# ProProject__-mpu6050__2024-04-23.net
KiCad netlist of a schematic drawn in EasyEDA Pro
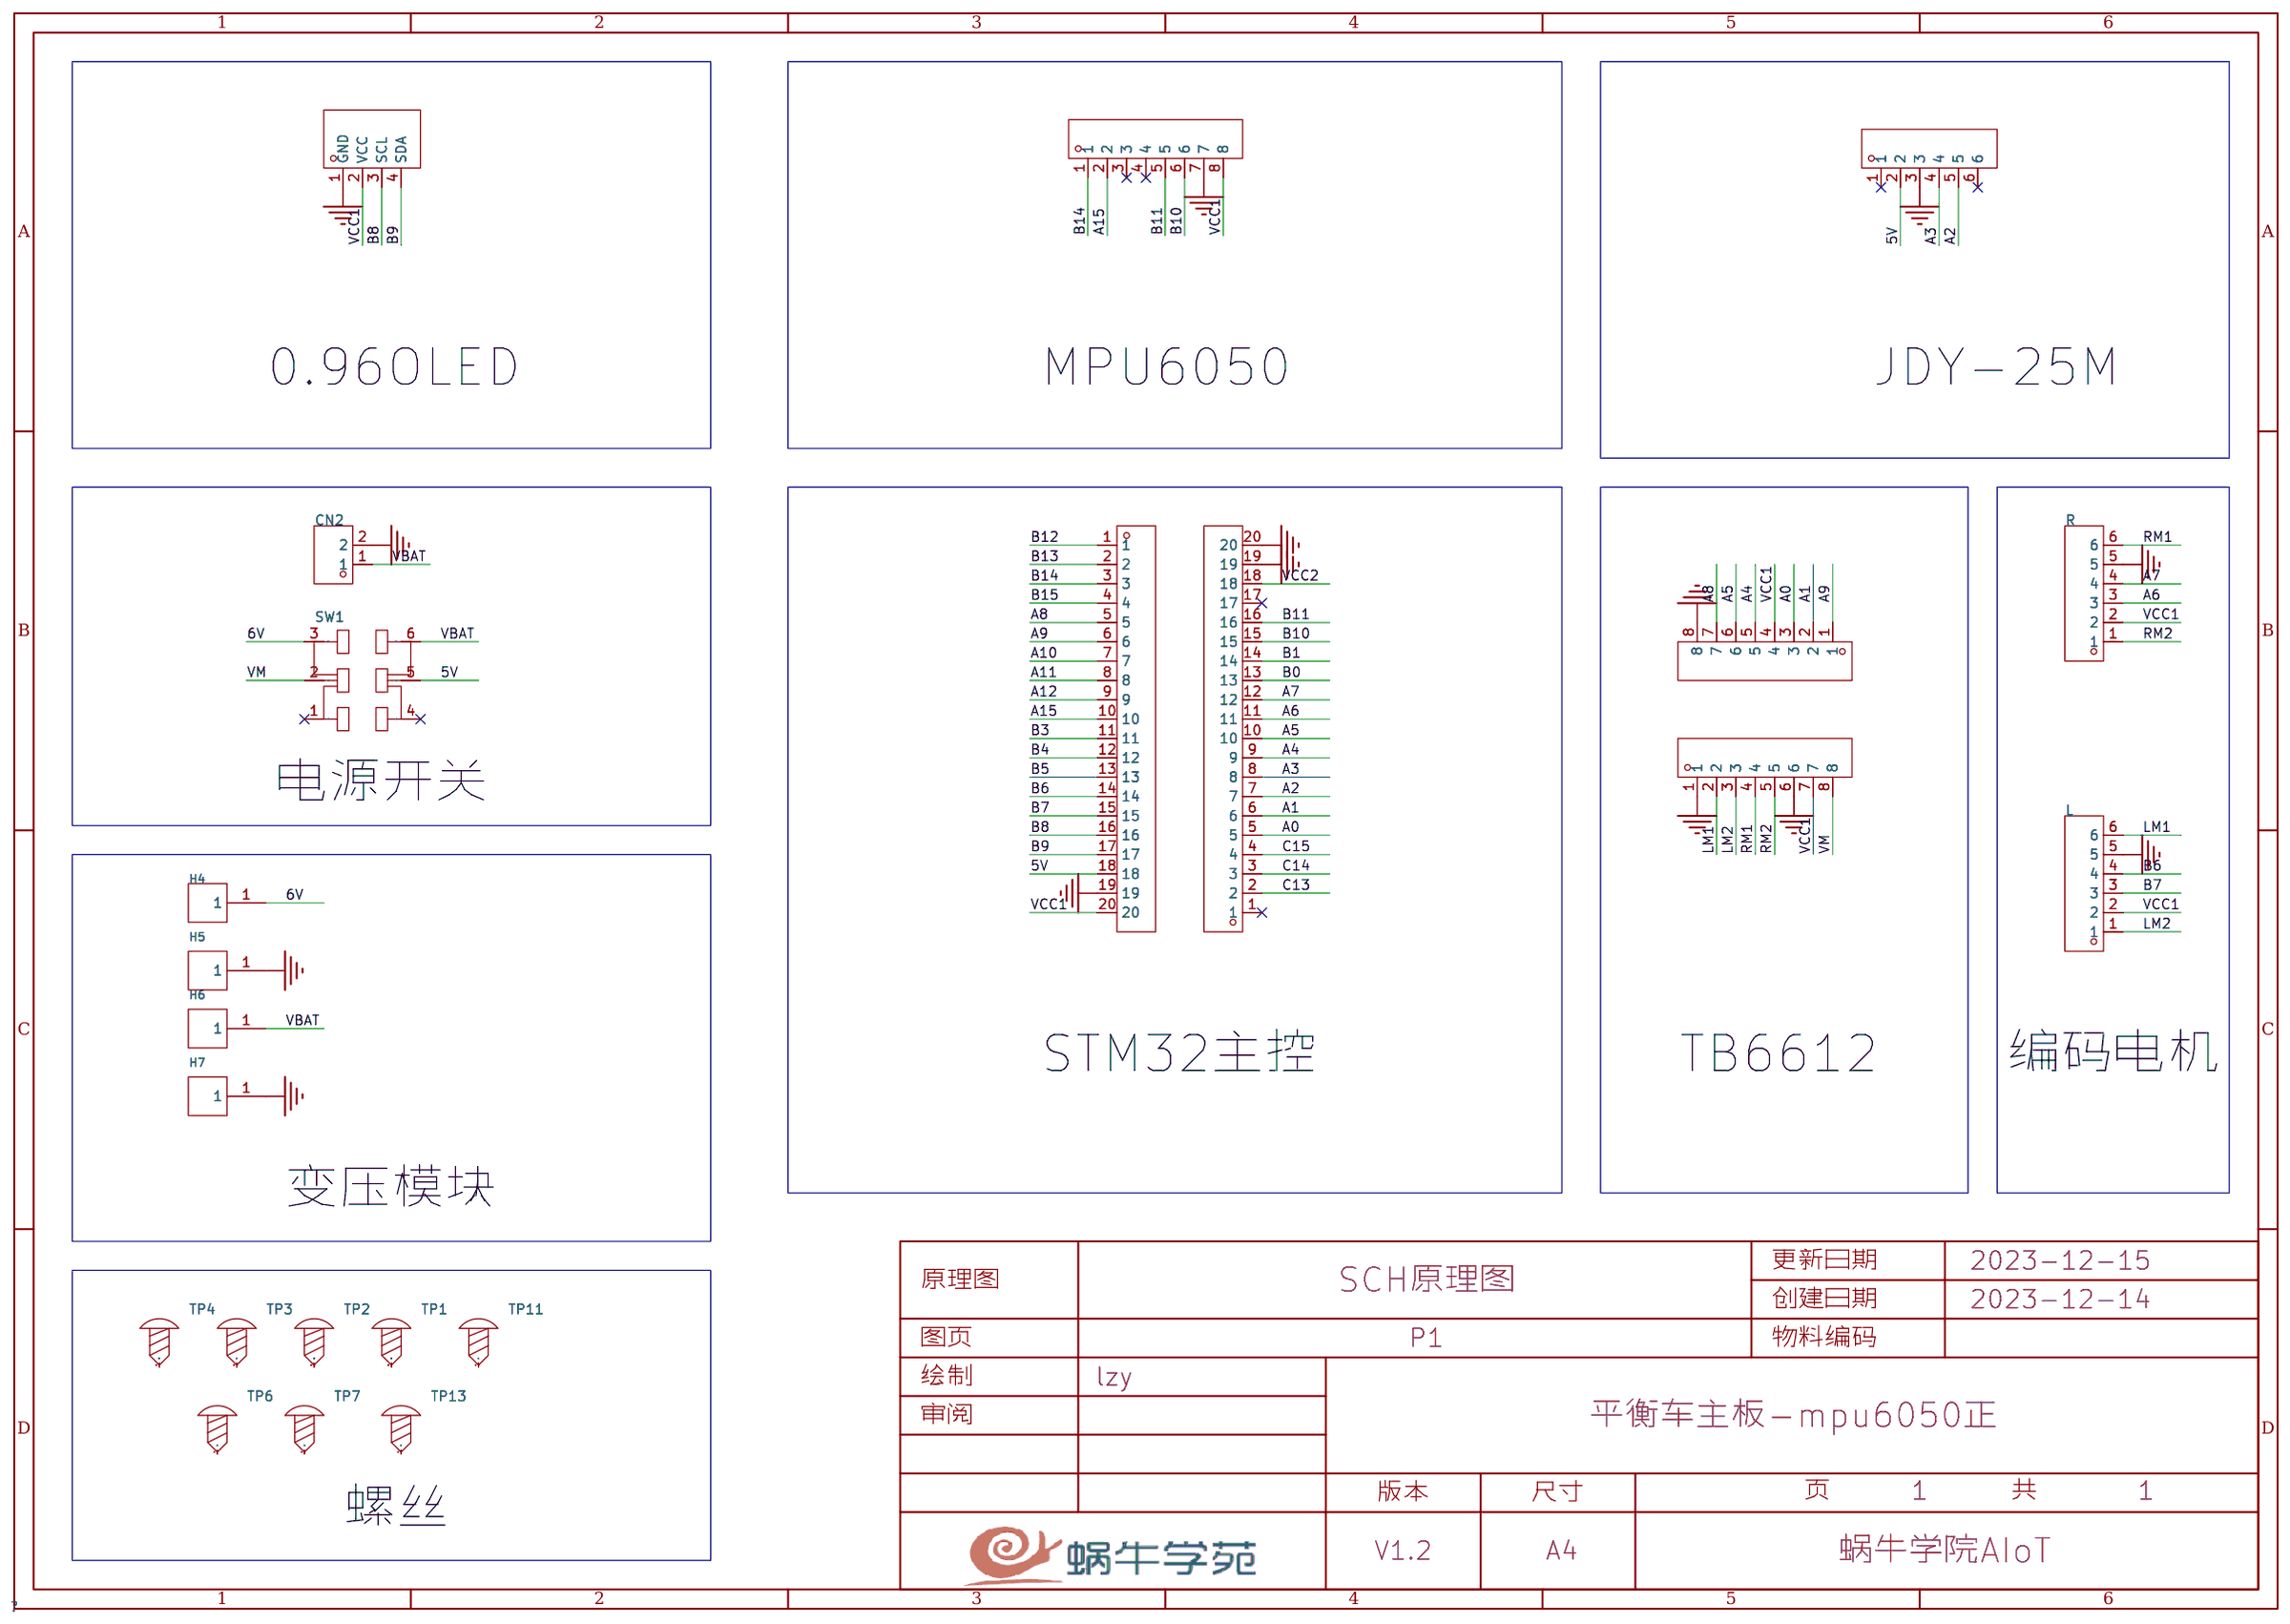
[diagram p0: schematic sheet]

(export (version "E")
  (design (tool "Eeschema 10.0.6"))
  (components
    (comp (ref "CN2")
      (value "XH-2AW")
      (footprint "easyedapro:CONN-TH_XH-2AW_C2908611")
      (description "插针结构:1x2P;间距:2.54mm;公母:公;安装方式:弯插;行距:-;排数:1;每排PIN数:2;参考系列:XH;额定电流:3A;工作温度范围:-25°C~+85°C;")
      (fields (field (name "Manufacturer") "HCTL(华灿天禄)"))
      (libsource (lib "easyedapro") (part "XH-2AW_C2908611"))
    )
    (comp (ref "H1")
      (value "PM254V-11-06-H85")
      (footprint "easyedapro:HDR-TH_6P-P2.54-V-F")
      (fields (field (name "Manufacturer") "XFCN(兴飞)"))
      (libsource (lib "easyedapro") (part "PM254V-11-06-H85"))
    )
    (comp (ref "H4")
      (value "PZ254V-11-01P")
      (footprint "easyedapro:HDR-TH_1P-P2.54-V-M")
      (fields (field (name "Manufacturer") "XFCN(兴飞)"))
      (libsource (lib "easyedapro") (part "PZ254V-11-01P"))
    )
    (comp (ref "H5")
      (value "PZ254V-11-01P")
      (footprint "easyedapro:HDR-TH_1P-P2.54-V-M")
      (fields (field (name "Manufacturer") "XFCN(兴飞)"))
      (libsource (lib "easyedapro") (part "PZ254V-11-01P"))
    )
    (comp (ref "H6")
      (value "PZ254V-11-01P")
      (footprint "easyedapro:HDR-TH_1P-P2.54-V-M")
      (fields (field (name "Manufacturer") "XFCN(兴飞)"))
      (libsource (lib "easyedapro") (part "PZ254V-11-01P"))
    )
    (comp (ref "H7")
      (value "PZ254V-11-01P")
      (footprint "easyedapro:HDR-TH_1P-P2.54-V-M")
      (fields (field (name "Manufacturer") "XFCN(兴飞)"))
      (libsource (lib "easyedapro") (part "PZ254V-11-01P"))
    )
    (comp (ref "L")
      (value "PM254V-11-06-H85")
      (footprint "easyedapro:HDR-TH_6P-P2.54-V-F")
      (fields (field (name "Manufacturer") "XFCN(兴飞)"))
      (libsource (lib "easyedapro") (part "PM254V-11-06-H85"))
    )
    (comp (ref "OLED")
      (value "HS96L03W2C03")
      (footprint "easyedapro:OLED-TH_L27.8-W27.2-P2.54_C9900033791")
      (fields (field (name "Manufacturer") "HS(汉昇)"))
      (libsource (lib "easyedapro") (part "HS96L03W2C03"))
    )
    (comp (ref "R")
      (value "PM254V-11-06-H85")
      (footprint "easyedapro:HDR-TH_6P-P2.54-V-F")
      (fields (field (name "Manufacturer") "XFCN(兴飞)"))
      (libsource (lib "easyedapro") (part "PM254V-11-06-H85"))
    )
    (comp (ref "SW1")
      (value "MSS22D18G2")
      (footprint "easyedapro:SW-TH_MSS22D18GX")
      (description "电路结构:双刀双掷;安装方式:立插;开关颜色:-;额定电流(DC):100mA;额定电压(DC):12V;额定电流(AC):-;额定电压(AC):-;机械寿命:1万次;")
      (fields (field (name "Manufacturer") "SHOU HAN(首韩)"))
      (libsource (lib "easyedapro") (part "MSS22D18G2"))
    )
    (comp (ref "TP1") (value "~") (footprint "easyedapro:M3螺丝") (libsource (lib "easyedapro") (part "螺丝孔")))
    (comp (ref "TP2") (value "~") (footprint "easyedapro:M3螺丝") (libsource (lib "easyedapro") (part "螺丝孔")))
    (comp (ref "TP3") (value "~") (footprint "easyedapro:M3螺丝") (libsource (lib "easyedapro") (part "螺丝孔")))
    (comp (ref "TP4") (value "~") (footprint "easyedapro:M3螺丝") (libsource (lib "easyedapro") (part "螺丝孔")))
    (comp (ref "TP6") (value "~") (footprint "easyedapro:M3螺丝") (libsource (lib "easyedapro") (part "螺丝孔")))
    (comp (ref "TP7") (value "~") (footprint "easyedapro:M3螺丝") (libsource (lib "easyedapro") (part "螺丝孔")))
    (comp (ref "TP11") (value "~") (footprint "easyedapro:M3螺丝") (libsource (lib "easyedapro") (part "螺丝孔")))
    (comp (ref "TP13") (value "~") (footprint "easyedapro:M3螺丝") (libsource (lib "easyedapro") (part "螺丝孔")))
    (comp (ref "U1")
      (value "PM254-1-20-Z-8.5")
      (footprint "easyedapro:HDR-TH_20P-P2.54-V-F-2")
      (fields (field (name "Manufacturer") "HCTL(华灿天禄)"))
      (libsource (lib "easyedapro") (part "PM254-1-20-Z-8.5"))
    )
    (comp (ref "U2")
      (value "PM254-1-20-Z-8.5")
      (footprint "easyedapro:HDR-TH_20P-P2.54-V-F-2")
      (fields (field (name "Manufacturer") "HCTL(华灿天禄)"))
      (libsource (lib "easyedapro") (part "PM254-1-20-Z-8.5"))
    )
    (comp (ref "U4")
      (value "PM254-1-08-Z-8.5")
      (footprint "easyedapro:HDR-TH_8P-P2.54-V-F")
      (fields (field (name "Manufacturer") "HCTL(华灿天禄)"))
      (libsource (lib "easyedapro") (part "PM254-1-08-Z-8.5"))
    )
    (comp (ref "U5")
      (value "PM254-1-08-Z-8.5")
      (footprint "easyedapro:HDR-TH_8P-P2.54-V-F")
      (fields (field (name "Manufacturer") "HCTL(华灿天禄)"))
      (libsource (lib "easyedapro") (part "PM254-1-08-Z-8.5"))
    )
    (comp (ref "U6")
      (value "PM254-1-08-Z-8.5")
      (footprint "easyedapro:HDR-TH_8P-P2.54-V-F")
      (fields (field (name "Manufacturer") "HCTL(华灿天禄)"))
      (libsource (lib "easyedapro") (part "PM254-1-08-Z-8.5"))
    )
  )
  (nets
    (net (code "1") (name "/5V") (class "Default")
      (node (ref "H1") (pin "2") (pinfunction "2_2") (pintype "unspecified"))
      (node (ref "SW1") (pin "5") (pinfunction "5_5") (pintype "unspecified"))
      (node (ref "U1") (pin "18") (pinfunction "18_18") (pintype "unspecified"))
    )
    (net (code "2") (name "/6V") (class "Default")
      (node (ref "H4") (pin "1") (pinfunction "1_1") (pintype "input"))
      (node (ref "SW1") (pin "3") (pinfunction "3_3") (pintype "unspecified"))
    )
    (net (code "3") (name "/A0") (class "Default")
      (node (ref "U2") (pin "5") (pinfunction "5_5") (pintype "unspecified"))
      (node (ref "U5") (pin "3") (pinfunction "3_3") (pintype "unspecified"))
    )
    (net (code "4") (name "/A1") (class "Default")
      (node (ref "U2") (pin "6") (pinfunction "6_6") (pintype "unspecified"))
      (node (ref "U5") (pin "2") (pinfunction "2_2") (pintype "unspecified"))
    )
    (net (code "5") (name "/A2") (class "Default")
      (node (ref "H1") (pin "5") (pinfunction "5_5") (pintype "unspecified"))
      (node (ref "U2") (pin "7") (pinfunction "7_7") (pintype "unspecified"))
    )
    (net (code "6") (name "/A3") (class "Default")
      (node (ref "H1") (pin "4") (pinfunction "4_4") (pintype "unspecified"))
      (node (ref "U2") (pin "8") (pinfunction "8_8") (pintype "unspecified"))
    )
    (net (code "7") (name "/A4") (class "Default")
      (node (ref "U2") (pin "9") (pinfunction "9_9") (pintype "unspecified"))
      (node (ref "U5") (pin "5") (pinfunction "5_5") (pintype "unspecified"))
    )
    (net (code "8") (name "/A5") (class "Default")
      (node (ref "U2") (pin "10") (pinfunction "10_10") (pintype "unspecified"))
      (node (ref "U5") (pin "6") (pinfunction "6_6") (pintype "unspecified"))
    )
    (net (code "9") (name "/A6") (class "Default")
      (node (ref "R") (pin "3") (pinfunction "3_3") (pintype "unspecified"))
      (node (ref "U2") (pin "11") (pinfunction "11_11") (pintype "unspecified"))
    )
    (net (code "10") (name "/A7") (class "Default")
      (node (ref "R") (pin "4") (pinfunction "4_4") (pintype "unspecified"))
      (node (ref "U2") (pin "12") (pinfunction "12_12") (pintype "unspecified"))
    )
    (net (code "11") (name "/A8") (class "Default")
      (node (ref "U1") (pin "5") (pinfunction "5_5") (pintype "unspecified"))
      (node (ref "U5") (pin "7") (pinfunction "7_7") (pintype "unspecified"))
    )
    (net (code "12") (name "/A9") (class "Default")
      (node (ref "U1") (pin "6") (pinfunction "6_6") (pintype "unspecified"))
      (node (ref "U5") (pin "1") (pinfunction "1_1") (pintype "unspecified"))
    )
    (net (code "13") (name "/A10") (class "Default")
      (node (ref "U1") (pin "7") (pinfunction "7_7") (pintype "unspecified"))
    )
    (net (code "14") (name "/A11") (class "Default")
      (node (ref "U1") (pin "8") (pinfunction "8_8") (pintype "unspecified"))
    )
    (net (code "15") (name "/A12") (class "Default")
      (node (ref "U1") (pin "9") (pinfunction "9_9") (pintype "unspecified"))
    )
    (net (code "16") (name "/A15") (class "Default")
      (node (ref "U1") (pin "10") (pinfunction "10_10") (pintype "unspecified"))
      (node (ref "U6") (pin "2") (pinfunction "2_2") (pintype "unspecified"))
    )
    (net (code "17") (name "/B0") (class "Default")
      (node (ref "U2") (pin "13") (pinfunction "13_13") (pintype "unspecified"))
    )
    (net (code "18") (name "/B1") (class "Default")
      (node (ref "U2") (pin "14") (pinfunction "14_14") (pintype "unspecified"))
    )
    (net (code "19") (name "/B3") (class "Default")
      (node (ref "U1") (pin "11") (pinfunction "11_11") (pintype "unspecified"))
    )
    (net (code "20") (name "/B4") (class "Default")
      (node (ref "U1") (pin "12") (pinfunction "12_12") (pintype "unspecified"))
    )
    (net (code "21") (name "/B5") (class "Default")
      (node (ref "U1") (pin "13") (pinfunction "13_13") (pintype "unspecified"))
    )
    (net (code "22") (name "/B6") (class "Default")
      (node (ref "L") (pin "4") (pinfunction "4_4") (pintype "unspecified"))
      (node (ref "U1") (pin "14") (pinfunction "14_14") (pintype "unspecified"))
    )
    (net (code "23") (name "/B7") (class "Default")
      (node (ref "L") (pin "3") (pinfunction "3_3") (pintype "unspecified"))
      (node (ref "U1") (pin "15") (pinfunction "15_15") (pintype "unspecified"))
    )
    (net (code "24") (name "/B8") (class "Default")
      (node (ref "OLED") (pin "3") (pinfunction "SCL_3") (pintype "unspecified"))
      (node (ref "U1") (pin "16") (pinfunction "16_16") (pintype "unspecified"))
    )
    (net (code "25") (name "/B9") (class "Default")
      (node (ref "OLED") (pin "4") (pinfunction "SDA_4") (pintype "unspecified"))
      (node (ref "U1") (pin "17") (pinfunction "17_17") (pintype "unspecified"))
    )
    (net (code "26") (name "/B10") (class "Default")
      (node (ref "U2") (pin "15") (pinfunction "15_15") (pintype "unspecified"))
      (node (ref "U6") (pin "6") (pinfunction "6_6") (pintype "unspecified"))
    )
    (net (code "27") (name "/B11") (class "Default")
      (node (ref "U2") (pin "16") (pinfunction "16_16") (pintype "unspecified"))
      (node (ref "U6") (pin "5") (pinfunction "5_5") (pintype "unspecified"))
    )
    (net (code "28") (name "/B12") (class "Default")
      (node (ref "U1") (pin "1") (pinfunction "1_1") (pintype "unspecified"))
    )
    (net (code "29") (name "/B13") (class "Default")
      (node (ref "U1") (pin "2") (pinfunction "2_2") (pintype "unspecified"))
    )
    (net (code "30") (name "/B14") (class "Default")
      (node (ref "U1") (pin "3") (pinfunction "3_3") (pintype "unspecified"))
      (node (ref "U6") (pin "1") (pinfunction "1_1") (pintype "unspecified"))
    )
    (net (code "31") (name "/B15") (class "Default")
      (node (ref "U1") (pin "4") (pinfunction "4_4") (pintype "unspecified"))
    )
    (net (code "32") (name "/C13") (class "Default")
      (node (ref "U2") (pin "2") (pinfunction "2_2") (pintype "unspecified"))
    )
    (net (code "33") (name "/C14") (class "Default")
      (node (ref "U2") (pin "3") (pinfunction "3_3") (pintype "unspecified"))
    )
    (net (code "34") (name "/C15") (class "Default")
      (node (ref "U2") (pin "4") (pinfunction "4_4") (pintype "unspecified"))
    )
    (net (code "35") (name "/LM1") (class "Default")
      (node (ref "L") (pin "6") (pinfunction "6_6") (pintype "unspecified"))
      (node (ref "U4") (pin "2") (pinfunction "2_2") (pintype "unspecified"))
    )
    (net (code "36") (name "/LM2") (class "Default")
      (node (ref "L") (pin "1") (pinfunction "1_1") (pintype "unspecified"))
      (node (ref "U4") (pin "3") (pinfunction "3_3") (pintype "unspecified"))
    )
    (net (code "37") (name "/RM1") (class "Default")
      (node (ref "R") (pin "6") (pinfunction "6_6") (pintype "unspecified"))
      (node (ref "U4") (pin "4") (pinfunction "4_4") (pintype "unspecified"))
    )
    (net (code "38") (name "/RM2") (class "Default")
      (node (ref "R") (pin "1") (pinfunction "1_1") (pintype "unspecified"))
      (node (ref "U4") (pin "5") (pinfunction "5_5") (pintype "unspecified"))
    )
    (net (code "39") (name "/VBAT") (class "Default")
      (node (ref "CN2") (pin "1") (pinfunction "1_1") (pintype "unspecified"))
      (node (ref "H6") (pin "1") (pinfunction "1_1") (pintype "input"))
      (node (ref "SW1") (pin "6") (pinfunction "6_6") (pintype "unspecified"))
    )
    (net (code "40") (name "/VCC1") (class "Default")
      (node (ref "L") (pin "2") (pinfunction "2_2") (pintype "unspecified"))
      (node (ref "OLED") (pin "2") (pinfunction "VCC_2") (pintype "unspecified"))
      (node (ref "R") (pin "2") (pinfunction "2_2") (pintype "unspecified"))
      (node (ref "U1") (pin "20") (pinfunction "20_20") (pintype "unspecified"))
      (node (ref "U4") (pin "7") (pinfunction "7_7") (pintype "unspecified"))
      (node (ref "U5") (pin "4") (pinfunction "4_4") (pintype "unspecified"))
      (node (ref "U6") (pin "8") (pinfunction "8_8") (pintype "unspecified"))
    )
    (net (code "41") (name "/VCC2") (class "Default")
      (node (ref "U2") (pin "18") (pinfunction "18_18") (pintype "unspecified"))
    )
    (net (code "42") (name "/VM") (class "Default")
      (node (ref "SW1") (pin "2") (pinfunction "2_2") (pintype "unspecified"))
      (node (ref "U4") (pin "8") (pinfunction "8_8") (pintype "unspecified"))
    )
    (net (code "43") (name "GND") (class "Default")
      (node (ref "CN2") (pin "2") (pinfunction "2_2") (pintype "unspecified"))
      (node (ref "H1") (pin "3") (pinfunction "3_3") (pintype "unspecified"))
      (node (ref "H5") (pin "1") (pinfunction "1_1") (pintype "input"))
      (node (ref "H7") (pin "1") (pinfunction "1_1") (pintype "input"))
      (node (ref "L") (pin "5") (pinfunction "5_5") (pintype "unspecified"))
      (node (ref "OLED") (pin "1") (pinfunction "GND_1") (pintype "unspecified"))
      (node (ref "R") (pin "5") (pinfunction "5_5") (pintype "unspecified"))
      (node (ref "U1") (pin "19") (pinfunction "19_19") (pintype "unspecified"))
      (node (ref "U2") (pin "19") (pinfunction "19_19") (pintype "unspecified"))
      (node (ref "U2") (pin "20") (pinfunction "20_20") (pintype "unspecified"))
      (node (ref "U4") (pin "1") (pinfunction "1_1") (pintype "unspecified"))
      (node (ref "U4") (pin "6") (pinfunction "6_6") (pintype "unspecified"))
      (node (ref "U5") (pin "8") (pinfunction "8_8") (pintype "unspecified"))
      (node (ref "U6") (pin "7") (pinfunction "7_7") (pintype "unspecified"))
    )
    (net (code "44") (name "unconnected-(H1-Pad1)") (class "Default")
      (node (ref "H1") (pin "1") (pinfunction "1_1") (pintype "unspecified+no_connect"))
    )
    (net (code "45") (name "unconnected-(H1-Pad6)") (class "Default")
      (node (ref "H1") (pin "6") (pinfunction "6_6") (pintype "unspecified+no_connect"))
    )
    (net (code "46") (name "unconnected-(SW1-Pad1)") (class "Default")
      (node (ref "SW1") (pin "1") (pinfunction "1_1") (pintype "unspecified+no_connect"))
    )
    (net (code "47") (name "unconnected-(SW1-Pad4)") (class "Default")
      (node (ref "SW1") (pin "4") (pinfunction "4_4") (pintype "unspecified+no_connect"))
    )
    (net (code "48") (name "unconnected-(TP1-Pad1)") (class "Default")
      (node (ref "TP1") (pin "1") (pinfunction "1_1") (pintype "input"))
    )
    (net (code "49") (name "unconnected-(TP2-Pad1)") (class "Default")
      (node (ref "TP2") (pin "1") (pinfunction "1_1") (pintype "input"))
    )
    (net (code "50") (name "unconnected-(TP3-Pad1)") (class "Default")
      (node (ref "TP3") (pin "1") (pinfunction "1_1") (pintype "input"))
    )
    (net (code "51") (name "unconnected-(TP4-Pad1)") (class "Default")
      (node (ref "TP4") (pin "1") (pinfunction "1_1") (pintype "input"))
    )
    (net (code "52") (name "unconnected-(TP6-Pad1)") (class "Default")
      (node (ref "TP6") (pin "1") (pinfunction "1_1") (pintype "input"))
    )
    (net (code "53") (name "unconnected-(TP7-Pad1)") (class "Default")
      (node (ref "TP7") (pin "1") (pinfunction "1_1") (pintype "input"))
    )
    (net (code "54") (name "unconnected-(TP11-Pad1)") (class "Default")
      (node (ref "TP11") (pin "1") (pinfunction "1_1") (pintype "input"))
    )
    (net (code "55") (name "unconnected-(TP13-Pad1)") (class "Default")
      (node (ref "TP13") (pin "1") (pinfunction "1_1") (pintype "input"))
    )
    (net (code "56") (name "unconnected-(U2-Pad1)") (class "Default")
      (node (ref "U2") (pin "1") (pinfunction "1_1") (pintype "unspecified+no_connect"))
    )
    (net (code "57") (name "unconnected-(U2-Pad17)") (class "Default")
      (node (ref "U2") (pin "17") (pinfunction "17_17") (pintype "unspecified+no_connect"))
    )
    (net (code "58") (name "unconnected-(U6-Pad3)") (class "Default")
      (node (ref "U6") (pin "3") (pinfunction "3_3") (pintype "unspecified+no_connect"))
    )
    (net (code "59") (name "unconnected-(U6-Pad4)") (class "Default")
      (node (ref "U6") (pin "4") (pinfunction "4_4") (pintype "unspecified+no_connect"))
    )
  )
)
